# schematic_easyeda.net
KiCad netlist of a schematic drawn in EasyEDA
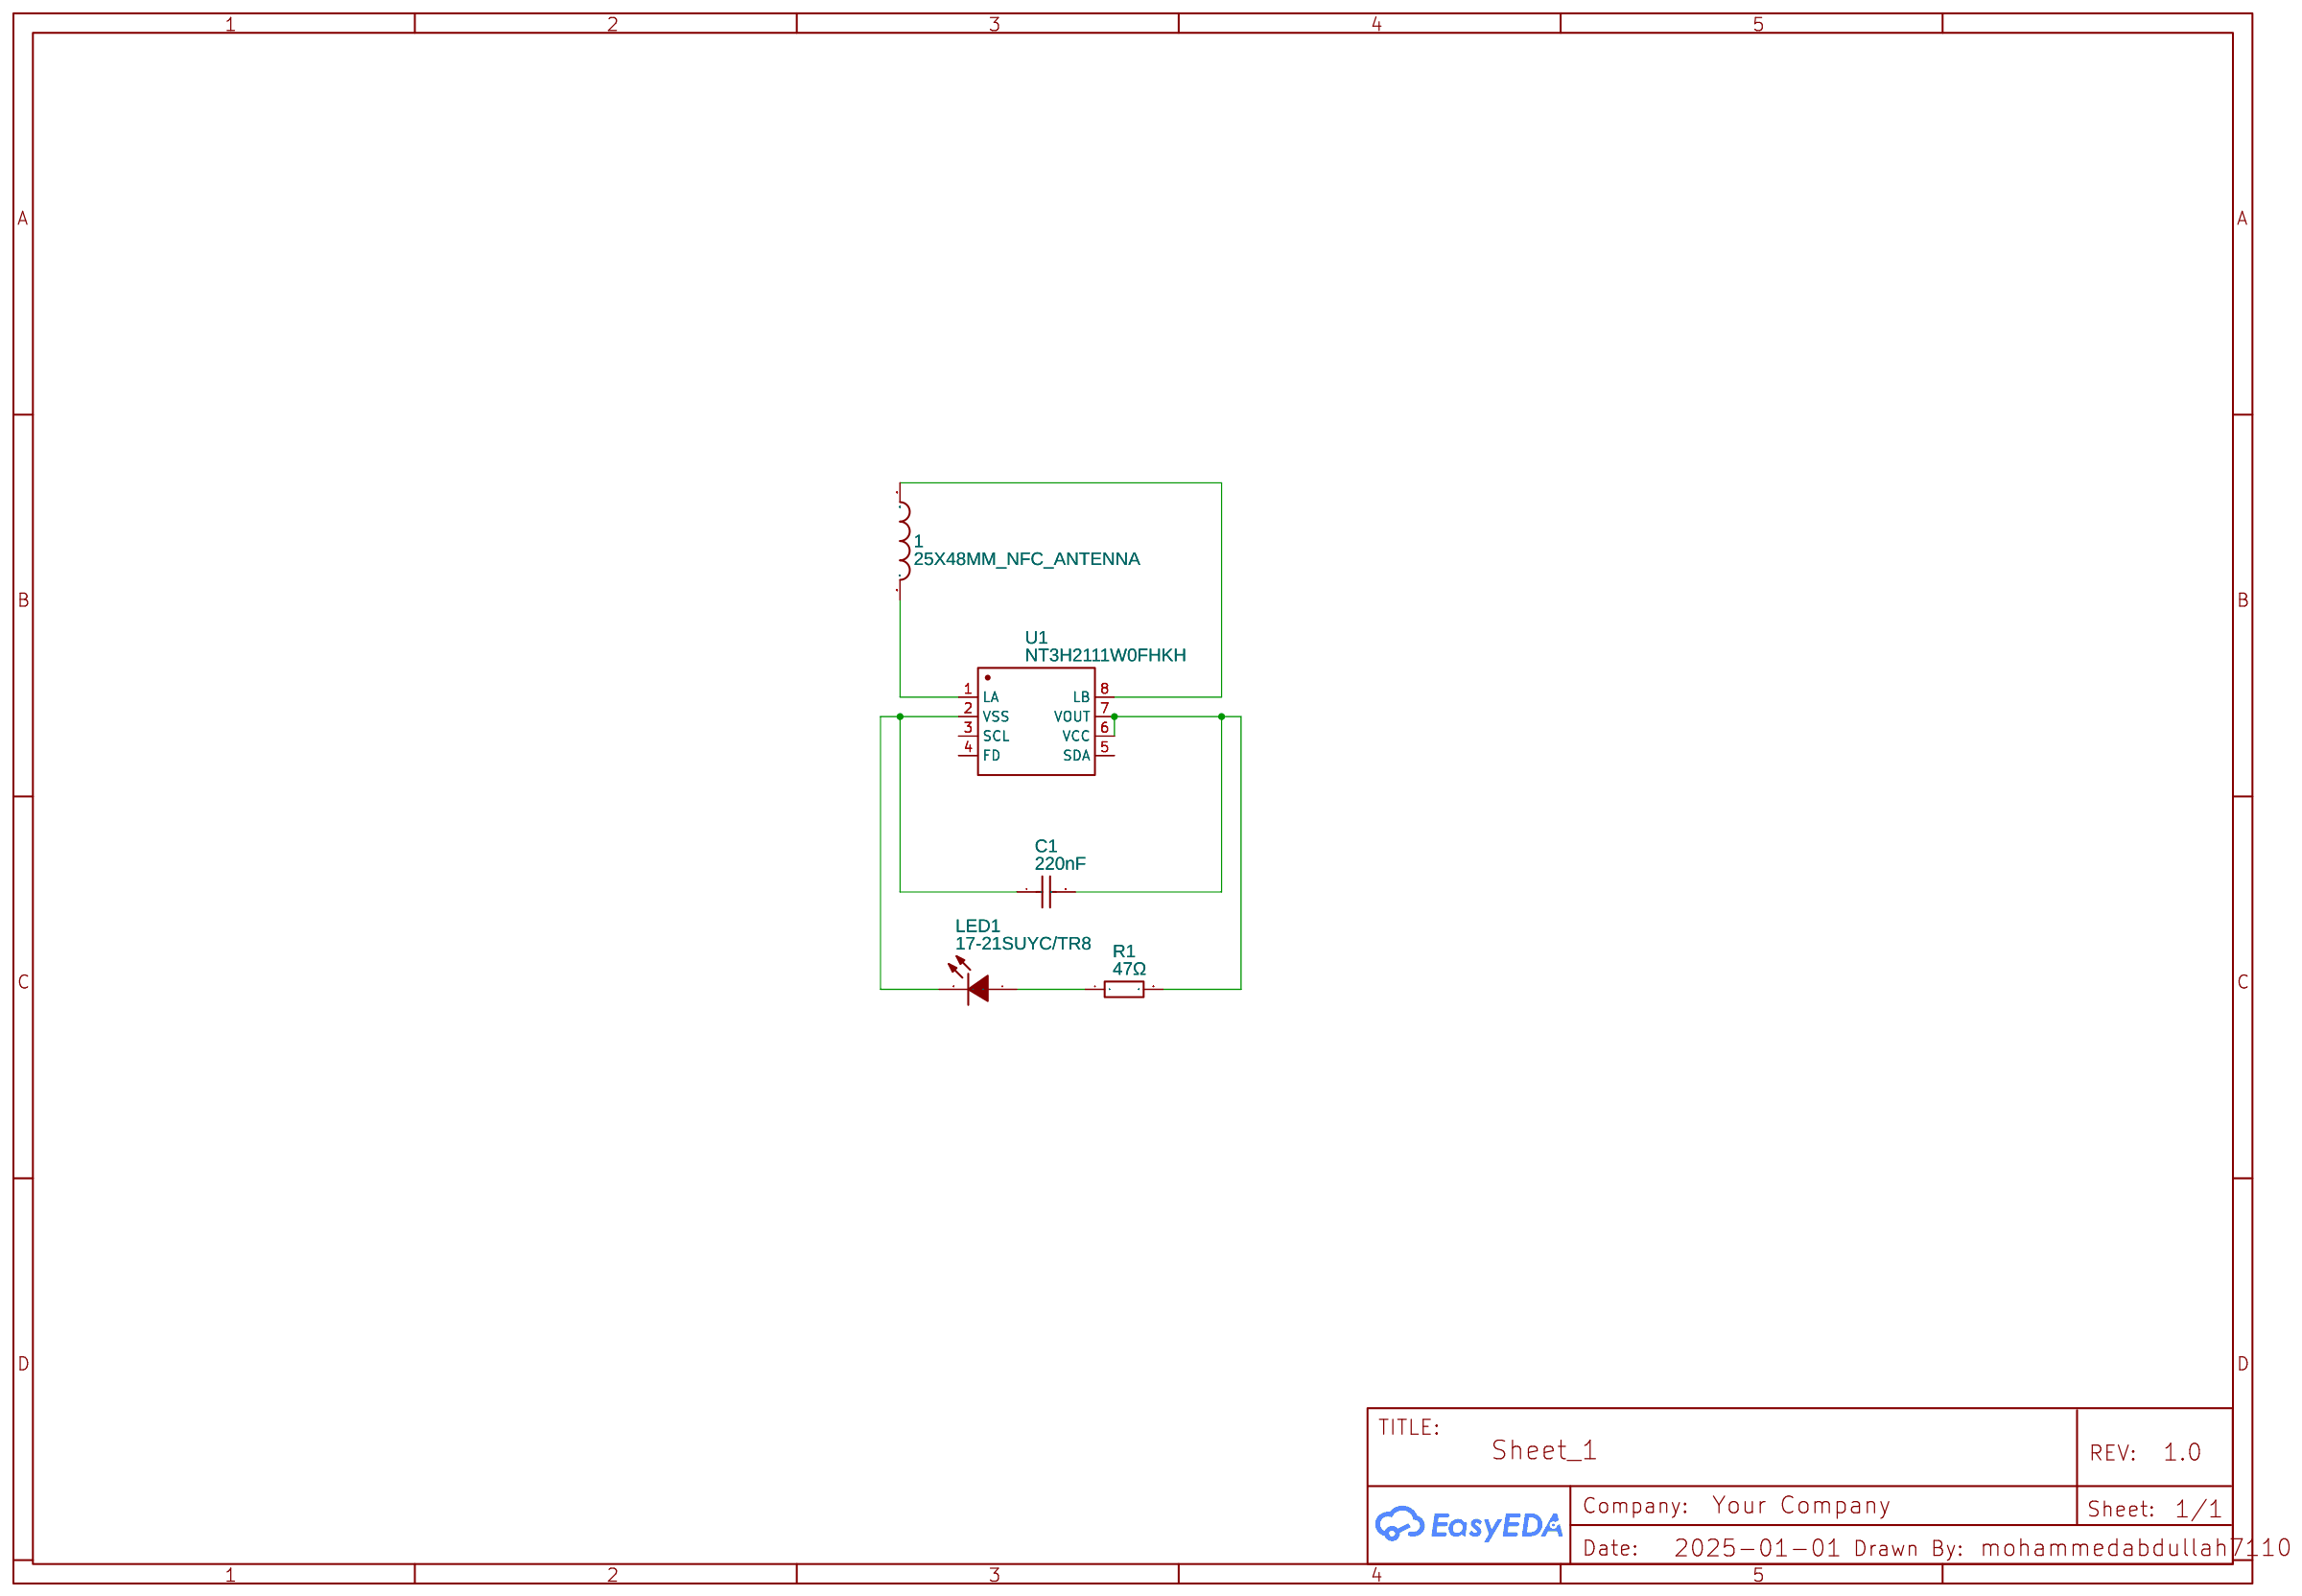
[diagram p0: schematic sheet]

(export (version "E")
  (design (tool "Eeschema 10.0.6"))
  (components
    (comp (ref "1") (value "25X48MM_NFC_ANTENNA") (libsource (lib "") (part "25X48MM_NFC_ANTENNA")))
    (comp (ref "C1")
      (value "220nF")
      (fields
        (field (name "Manufacturer Part") "CL10B224KA8NNNC")
        (field (name "Manufacturer") "SAMSUNG(三星)")
      )
      (libsource (lib "") (part "CL10B224KA8NNNC"))
    )
    (comp (ref "LED1")
      (value "17-21SUYC/TR8")
      (fields (field (name "Manufacturer Part") "KT-0805黄灯") (field (name "Manufacturer") "KENTO"))
      (libsource (lib "") (part "17-21SUYC/TR8"))
    )
    (comp (ref "R1")
      (value "47Ω")
      (fields
        (field (name "Manufacturer Part") "0603WAF470JT5E")
        (field (name "Manufacturer") "UNI-ROYAL(厚声)")
      )
      (libsource (lib "") (part "0603WAF470JT5E"))
    )
    (comp (ref "U1")
      (value "NT3H2111W0FHKH")
      (fields (field (name "Manufacturer") "NXP(恩智浦)"))
      (libsource (lib "") (part "NT3H2111W0FHKH"))
    )
  )
  (nets
    (net (code "1") (name "Net-(LED1-+)") (class "Default")
      (node (ref "LED1") (pin "1") (pinfunction "+_1") (pintype "unspecified"))
      (node (ref "R1") (pin "1") (pinfunction "1_1") (pintype "input"))
    )
    (net (code "2") (name "Net-(LED1--)") (class "Default")
      (node (ref "C1") (pin "1") (pinfunction "1_1") (pintype "input"))
      (node (ref "LED1") (pin "2") (pinfunction "-_2") (pintype "unspecified"))
      (node (ref "U1") (pin "2") (pinfunction "VSS_2") (pintype "unspecified"))
    )
    (net (code "3") (name "Net-(U1-LA)") (class "Default")
      (node (ref "1") (pin "P$2") (pinfunction "P$2_P$2") (pintype "bidirectional"))
      (node (ref "U1") (pin "1") (pinfunction "LA_1") (pintype "unspecified"))
    )
    (net (code "4") (name "Net-(U1-LB)") (class "Default")
      (node (ref "1") (pin "P$1") (pinfunction "P$1_P$1") (pintype "bidirectional"))
      (node (ref "U1") (pin "8") (pinfunction "LB_8") (pintype "unspecified"))
    )
    (net (code "5") (name "Net-(U1-VCC)") (class "Default")
      (node (ref "C1") (pin "2") (pinfunction "2_2") (pintype "input"))
      (node (ref "R1") (pin "2") (pinfunction "2_2") (pintype "input"))
      (node (ref "U1") (pin "6") (pinfunction "VCC_6") (pintype "unspecified"))
      (node (ref "U1") (pin "7") (pinfunction "VOUT_7") (pintype "unspecified"))
    )
    (net (code "6") (name "unconnected-(U1-FD-Pad4)") (class "Default")
      (node (ref "U1") (pin "4") (pinfunction "FD_4") (pintype "unspecified"))
    )
    (net (code "7") (name "unconnected-(U1-SCL-Pad3)") (class "Default")
      (node (ref "U1") (pin "3") (pinfunction "SCL_3") (pintype "unspecified"))
    )
    (net (code "8") (name "unconnected-(U1-SDA-Pad5)") (class "Default")
      (node (ref "U1") (pin "5") (pinfunction "SDA_5") (pintype "unspecified"))
    )
  )
)
